# rca_studio_II_mutli_v5.net
KiCad netlist of a schematic drawn in EAGLE
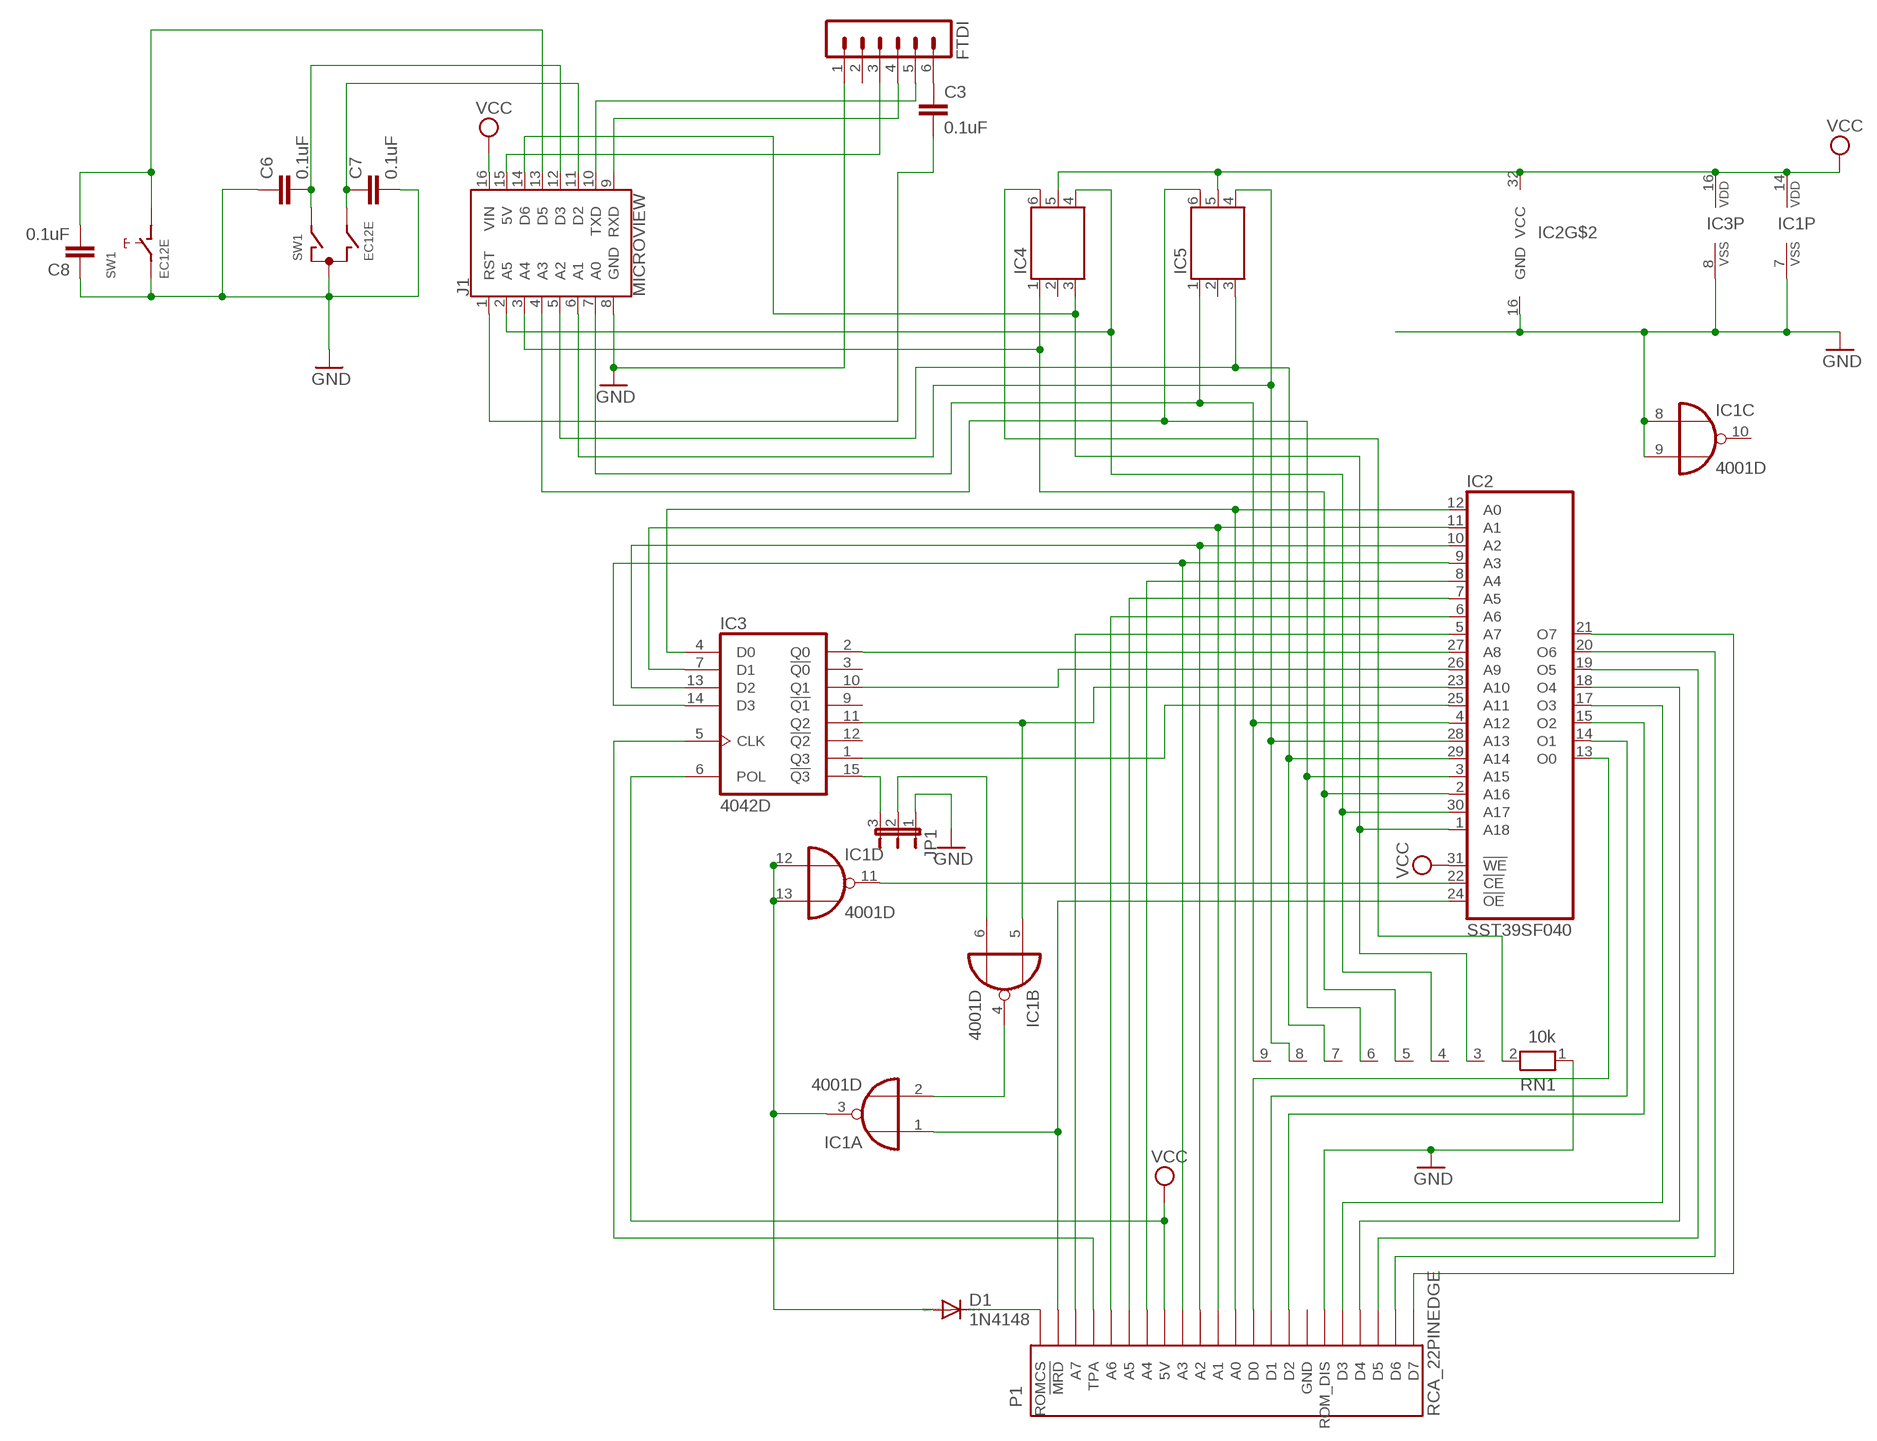
[diagram p0: schematic, sheet 1]

(export (version "E")
  (design (tool "Eeschema 10.0.6"))
  (components
    (comp (ref "C3")
      (value "0.1uF")
      (footprint "eagle-import:C0805")
      (libsource (lib "eagle-import") (part "C-EUC0805"))
    )
    (comp (ref "C6")
      (value "0.1uF")
      (footprint "eagle-import:C0805")
      (libsource (lib "eagle-import") (part "C-EUC0805"))
    )
    (comp (ref "C7")
      (value "0.1uF")
      (footprint "eagle-import:C0805")
      (libsource (lib "eagle-import") (part "C-EUC0805"))
    )
    (comp (ref "C8")
      (value "0.1uF")
      (footprint "eagle-import:C0805")
      (libsource (lib "eagle-import") (part "C-EUC0805"))
    )
    (comp (ref "D1")
      (value "1N4148")
      (footprint "eagle-import:DO35-7")
      (libsource (lib "eagle-import") (part "1N4148DO35-7"))
    )
    (comp (ref "FTDI")
      (value "MA06-1")
      (footprint "eagle-import:MA06-1")
      (libsource (lib "eagle-import") (part "MA06-1"))
    )
    (comp (ref "IC1")
      (value "4001D")
      (footprint "eagle-import:SO14")
      (libsource (lib "eagle-import") (part "4001D"))
    )
    (comp (ref "IC2")
      (value "SST39SF040")
      (footprint "eagle-import:S32")
      (libsource (lib "eagle-import") (part "SST39SF040"))
    )
    (comp (ref "IC3")
      (value "4042D")
      (footprint "eagle-import:SO16")
      (libsource (lib "eagle-import") (part "4042D"))
    )
    (comp (ref "IC4")
      (value "HEXENCODERHEXENCODER")
      (footprint "eagle-import:HEXENCODER")
      (libsource (lib "eagle-import") (part "HEXENCODERHEXENCODER"))
    )
    (comp (ref "IC5")
      (value "HEXENCODERHEXENCODER")
      (footprint "eagle-import:HEXENCODER")
      (libsource (lib "eagle-import") (part "HEXENCODERHEXENCODER"))
    )
    (comp (ref "J1")
      (value "MICROVIEW")
      (footprint "eagle-import:MV-DIP16-NODIMENSION")
      (libsource (lib "eagle-import") (part "MICROVIEW-16ND"))
    )
    (comp (ref "JP1")
      (value "JP2E")
      (footprint "eagle-import:JP2")
      (libsource (lib "eagle-import") (part "JP2E"))
    )
    (comp (ref "P1")
      (value "RCA_22PINEDGE")
      (footprint "eagle-import:RCA_22PINEDGE")
      (libsource (lib "eagle-import") (part "RCA_22PINEDGE"))
    )
    (comp (ref "RN1")
      (value "10k")
      (footprint "eagle-import:RN-9")
      (libsource (lib "eagle-import") (part "RN08"))
    )
    (comp (ref "SW1")
      (value "EC12E")
      (footprint "eagle-import:ALPS_EC12E_SW")
      (fields (field (name "MPN") "EC12E2424407"))
      (libsource (lib "eagle-import") (part "EC12E_SW"))
    )
  )
  (nets
    (net (code "1") (name "GND") (class "Default")
      (node (ref "C6") (pin "1") (pinfunction "1_1") (pintype "passive"))
      (node (ref "C7") (pin "2") (pinfunction "2_2") (pintype "passive"))
      (node (ref "C8") (pin "1") (pinfunction "1_1") (pintype "passive"))
      (node (ref "FTDI") (pin "1") (pinfunction "1_1") (pintype "passive"))
      (node (ref "IC1") (pin "7") (pinfunction "VSS_7") (pintype "power_in"))
      (node (ref "IC1") (pin "8") (pinfunction "I0_8") (pintype "input"))
      (node (ref "IC1") (pin "9") (pinfunction "I1_9") (pintype "input"))
      (node (ref "IC2") (pin "16") (pinfunction "GND_16") (pintype "power_in"))
      (node (ref "IC3") (pin "8") (pinfunction "VSS_8") (pintype "power_in"))
      (node (ref "J1") (pin "8") (pinfunction "GND_8") (pintype "power_in"))
      (node (ref "JP1") (pin "1") (pinfunction "1_1") (pintype "passive"))
      (node (ref "P1") (pin "6") (pinfunction "ROM_DIS_6") (pintype "passive"))
      (node (ref "RN1") (pin "1") (pinfunction "1_1") (pintype "passive"))
      (node (ref "SW1") (pin "C") (pinfunction "C_C") (pintype "passive"))
      (node (ref "SW1") (pin "E") (pinfunction "2_E") (pintype "passive"))
    )
    (net (code "2") (name "Net-(C3-Pad1)") (class "Default")
      (node (ref "C3") (pin "1") (pinfunction "1_1") (pintype "passive"))
      (node (ref "FTDI") (pin "6") (pinfunction "6_6") (pintype "passive"))
    )
    (net (code "3") (name "Net-(IC1A-I0)") (class "Default")
      (node (ref "IC1") (pin "1") (pinfunction "I0_1") (pintype "input"))
      (node (ref "IC2") (pin "24") (pinfunction "~{OE}_24") (pintype "input"))
      (node (ref "P1") (pin "21") (pinfunction "~{MRD}_21") (pintype "passive"))
    )
    (net (code "4") (name "Net-(IC1A-I1)") (class "Default")
      (node (ref "IC1") (pin "2") (pinfunction "I1_2") (pintype "input"))
      (node (ref "IC1") (pin "4") (pinfunction "O_4") (pintype "output"))
    )
    (net (code "5") (name "Net-(IC1A-O)") (class "Default")
      (node (ref "D1") (pin "A") (pinfunction "A_A") (pintype "passive"))
      (node (ref "IC1") (pin "12") (pinfunction "I0_12") (pintype "input"))
      (node (ref "IC1") (pin "13") (pinfunction "I1_13") (pintype "input"))
      (node (ref "IC1") (pin "3") (pinfunction "O_3") (pintype "output"))
    )
    (net (code "6") (name "Net-(IC1B-I0)") (class "Default")
      (node (ref "IC1") (pin "5") (pinfunction "I0_5") (pintype "input"))
      (node (ref "IC2") (pin "23") (pinfunction "A10_23") (pintype "input"))
      (node (ref "IC3") (pin "11") (pinfunction "Q2_11") (pintype "output"))
    )
    (net (code "7") (name "Net-(IC1B-I1)") (class "Default")
      (node (ref "IC1") (pin "6") (pinfunction "I1_6") (pintype "input"))
      (node (ref "JP1") (pin "2") (pinfunction "2_2") (pintype "passive"))
    )
    (net (code "8") (name "Net-(IC1D-O)") (class "Default")
      (node (ref "IC1") (pin "11") (pinfunction "O_11") (pintype "output"))
      (node (ref "IC2") (pin "22") (pinfunction "~{CE}_22") (pintype "input"))
    )
    (net (code "9") (name "Net-(IC2A-A0)") (class "Default")
      (node (ref "IC2") (pin "12") (pinfunction "A0_12") (pintype "input"))
      (node (ref "IC3") (pin "4") (pinfunction "D0_4") (pintype "input"))
      (node (ref "P1") (pin "11") (pinfunction "A0_11") (pintype "passive"))
    )
    (net (code "10") (name "Net-(IC2A-A1)") (class "Default")
      (node (ref "IC2") (pin "11") (pinfunction "A1_11") (pintype "input"))
      (node (ref "IC3") (pin "7") (pinfunction "D1_7") (pintype "input"))
      (node (ref "P1") (pin "12") (pinfunction "A1_12") (pintype "passive"))
    )
    (net (code "11") (name "Net-(IC2A-A2)") (class "Default")
      (node (ref "IC2") (pin "10") (pinfunction "A2_10") (pintype "input"))
      (node (ref "IC3") (pin "13") (pinfunction "D2_13") (pintype "input"))
      (node (ref "P1") (pin "13") (pinfunction "A2_13") (pintype "passive"))
    )
    (net (code "12") (name "Net-(IC2A-A3)") (class "Default")
      (node (ref "IC2") (pin "9") (pinfunction "A3_9") (pintype "input"))
      (node (ref "IC3") (pin "14") (pinfunction "D3_14") (pintype "input"))
      (node (ref "P1") (pin "14") (pinfunction "A3_14") (pintype "passive"))
    )
    (net (code "13") (name "Net-(IC2A-A4)") (class "Default")
      (node (ref "IC2") (pin "8") (pinfunction "A4_8") (pintype "input"))
      (node (ref "P1") (pin "16") (pinfunction "A4_16") (pintype "passive"))
    )
    (net (code "14") (name "Net-(IC2A-A5)") (class "Default")
      (node (ref "IC2") (pin "7") (pinfunction "A5_7") (pintype "input"))
      (node (ref "P1") (pin "17") (pinfunction "A5_17") (pintype "passive"))
    )
    (net (code "15") (name "Net-(IC2A-A6)") (class "Default")
      (node (ref "IC2") (pin "6") (pinfunction "A6_6") (pintype "input"))
      (node (ref "P1") (pin "18") (pinfunction "A6_18") (pintype "passive"))
    )
    (net (code "16") (name "Net-(IC2A-A7)") (class "Default")
      (node (ref "IC2") (pin "5") (pinfunction "A7_5") (pintype "input"))
      (node (ref "P1") (pin "20") (pinfunction "A7_20") (pintype "passive"))
    )
    (net (code "17") (name "Net-(IC2A-A8)") (class "Default")
      (node (ref "IC2") (pin "27") (pinfunction "A8_27") (pintype "input"))
      (node (ref "IC3") (pin "2") (pinfunction "Q0_2") (pintype "output"))
    )
    (net (code "18") (name "Net-(IC2A-A9)") (class "Default")
      (node (ref "IC2") (pin "26") (pinfunction "A9_26") (pintype "input"))
      (node (ref "IC3") (pin "10") (pinfunction "Q1_10") (pintype "output"))
    )
    (net (code "19") (name "Net-(IC2A-A11)") (class "Default")
      (node (ref "IC2") (pin "25") (pinfunction "A11_25") (pintype "input"))
      (node (ref "IC3") (pin "1") (pinfunction "Q3_1") (pintype "output"))
    )
    (net (code "20") (name "Net-(IC2A-A12)") (class "Default")
      (node (ref "IC2") (pin "4") (pinfunction "A12_4") (pintype "input"))
      (node (ref "IC5") (pin "1") (pinfunction "1_1") (pintype "passive"))
      (node (ref "J1") (pin "7") (pinfunction "A0_7") (pintype "output"))
      (node (ref "RN1") (pin "9") (pinfunction "9_9") (pintype "passive"))
    )
    (net (code "21") (name "Net-(IC2A-A13)") (class "Default")
      (node (ref "IC2") (pin "28") (pinfunction "A13_28") (pintype "input"))
      (node (ref "IC5") (pin "4") (pinfunction "2_4") (pintype "passive"))
      (node (ref "J1") (pin "6") (pinfunction "A1_6") (pintype "output"))
      (node (ref "RN1") (pin "8") (pinfunction "8_8") (pintype "passive"))
    )
    (net (code "22") (name "Net-(IC2A-A14)") (class "Default")
      (node (ref "IC2") (pin "29") (pinfunction "A14_29") (pintype "input"))
      (node (ref "IC5") (pin "3") (pinfunction "4_3") (pintype "passive"))
      (node (ref "J1") (pin "5") (pinfunction "A2_5") (pintype "output"))
      (node (ref "RN1") (pin "7") (pinfunction "7_7") (pintype "passive"))
    )
    (net (code "23") (name "Net-(IC2A-A15)") (class "Default")
      (node (ref "IC2") (pin "3") (pinfunction "A15_3") (pintype "input"))
      (node (ref "IC5") (pin "6") (pinfunction "8_6") (pintype "passive"))
      (node (ref "J1") (pin "4") (pinfunction "A3_4") (pintype "output"))
      (node (ref "RN1") (pin "6") (pinfunction "6_6") (pintype "passive"))
    )
    (net (code "24") (name "Net-(IC2A-A16)") (class "Default")
      (node (ref "IC2") (pin "2") (pinfunction "A16_2") (pintype "input"))
      (node (ref "IC4") (pin "1") (pinfunction "1_1") (pintype "passive"))
      (node (ref "J1") (pin "3") (pinfunction "A4_3") (pintype "output"))
      (node (ref "RN1") (pin "5") (pinfunction "5_5") (pintype "passive"))
    )
    (net (code "25") (name "Net-(IC2A-A17)") (class "Default")
      (node (ref "IC2") (pin "30") (pinfunction "A17_30") (pintype "input"))
      (node (ref "IC4") (pin "4") (pinfunction "2_4") (pintype "passive"))
      (node (ref "J1") (pin "2") (pinfunction "A5_2") (pintype "output"))
      (node (ref "RN1") (pin "4") (pinfunction "4_4") (pintype "passive"))
    )
    (net (code "26") (name "Net-(IC2A-A18)") (class "Default")
      (node (ref "IC2") (pin "1") (pinfunction "A18_1") (pintype "input"))
      (node (ref "IC4") (pin "3") (pinfunction "4_3") (pintype "passive"))
      (node (ref "J1") (pin "14") (pinfunction "D6_14") (pintype "output"))
      (node (ref "RN1") (pin "3") (pinfunction "3_3") (pintype "passive"))
    )
    (net (code "27") (name "Net-(IC2A-O0)") (class "Default")
      (node (ref "IC2") (pin "13") (pinfunction "O0_13") (pintype "tri_state"))
      (node (ref "P1") (pin "10") (pinfunction "D0_10") (pintype "passive"))
    )
    (net (code "28") (name "Net-(IC2A-O1)") (class "Default")
      (node (ref "IC2") (pin "14") (pinfunction "O1_14") (pintype "tri_state"))
      (node (ref "P1") (pin "9") (pinfunction "D1_9") (pintype "passive"))
    )
    (net (code "29") (name "Net-(IC2A-O2)") (class "Default")
      (node (ref "IC2") (pin "15") (pinfunction "O2_15") (pintype "tri_state"))
      (node (ref "P1") (pin "8") (pinfunction "D2_8") (pintype "passive"))
    )
    (net (code "30") (name "Net-(IC2A-O3)") (class "Default")
      (node (ref "IC2") (pin "17") (pinfunction "O3_17") (pintype "tri_state"))
      (node (ref "P1") (pin "5") (pinfunction "D3_5") (pintype "passive"))
    )
    (net (code "31") (name "Net-(IC2A-O4)") (class "Default")
      (node (ref "IC2") (pin "18") (pinfunction "O4_18") (pintype "tri_state"))
      (node (ref "P1") (pin "4") (pinfunction "D4_4") (pintype "passive"))
    )
    (net (code "32") (name "Net-(IC2A-O5)") (class "Default")
      (node (ref "IC2") (pin "19") (pinfunction "O5_19") (pintype "tri_state"))
      (node (ref "P1") (pin "3") (pinfunction "D5_3") (pintype "passive"))
    )
    (net (code "33") (name "Net-(IC2A-O6)") (class "Default")
      (node (ref "IC2") (pin "20") (pinfunction "O6_20") (pintype "tri_state"))
      (node (ref "P1") (pin "2") (pinfunction "D6_2") (pintype "passive"))
    )
    (net (code "34") (name "Net-(IC2A-O7)") (class "Default")
      (node (ref "IC2") (pin "21") (pinfunction "O7_21") (pintype "tri_state"))
      (node (ref "P1") (pin "1") (pinfunction "D7_1") (pintype "passive"))
    )
    (net (code "35") (name "Net-(IC3A-CLK)") (class "Default")
      (node (ref "IC3") (pin "5") (pinfunction "CLK_5") (pintype "input"))
      (node (ref "P1") (pin "19") (pinfunction "TPA_19") (pintype "passive"))
    )
    (net (code "36") (name "Net-(IC3A-~{Q3})") (class "Default")
      (node (ref "IC3") (pin "15") (pinfunction "~{Q3}_15") (pintype "output"))
      (node (ref "JP1") (pin "3") (pinfunction "3_3") (pintype "passive"))
    )
    (net (code "37") (name "Net-(IC4-8)") (class "Default")
      (node (ref "IC4") (pin "6") (pinfunction "8_6") (pintype "passive"))
      (node (ref "RN1") (pin "2") (pinfunction "2_2") (pintype "passive"))
    )
    (net (code "38") (name "Net-(J1-5V)") (class "Default")
      (node (ref "FTDI") (pin "3") (pinfunction "3_3") (pintype "passive"))
      (node (ref "J1") (pin "15") (pinfunction "5V_15") (pintype "output"))
    )
    (net (code "39") (name "Net-(J1-D2)") (class "Default")
      (node (ref "C7") (pin "1") (pinfunction "1_1") (pintype "passive"))
      (node (ref "J1") (pin "11") (pinfunction "D2_11") (pintype "output"))
      (node (ref "SW1") (pin "B") (pinfunction "B_B") (pintype "passive"))
    )
    (net (code "40") (name "Net-(J1-D3)") (class "Default")
      (node (ref "C6") (pin "2") (pinfunction "2_2") (pintype "passive"))
      (node (ref "J1") (pin "12") (pinfunction "D3_12") (pintype "output"))
      (node (ref "SW1") (pin "A") (pinfunction "A_A") (pintype "passive"))
    )
    (net (code "41") (name "Net-(J1-D5)") (class "Default")
      (node (ref "C8") (pin "2") (pinfunction "2_2") (pintype "passive"))
      (node (ref "J1") (pin "13") (pinfunction "D5_13") (pintype "output"))
      (node (ref "SW1") (pin "D") (pinfunction "1_D") (pintype "passive"))
    )
    (net (code "42") (name "Net-(J1-RST)") (class "Default")
      (node (ref "C3") (pin "2") (pinfunction "2_2") (pintype "passive"))
      (node (ref "J1") (pin "1") (pinfunction "RST_1") (pintype "output"))
    )
    (net (code "43") (name "Net-(J1-RXD)") (class "Default")
      (node (ref "FTDI") (pin "4") (pinfunction "4_4") (pintype "passive"))
      (node (ref "J1") (pin "9") (pinfunction "RXD_9") (pintype "output"))
    )
    (net (code "44") (name "Net-(J1-TXD)") (class "Default")
      (node (ref "FTDI") (pin "5") (pinfunction "5_5") (pintype "passive"))
      (node (ref "J1") (pin "10") (pinfunction "TXD_10") (pintype "output"))
    )
    (net (code "45") (name "Net-(P1-ROMCS)") (class "Default")
      (node (ref "D1") (pin "C") (pinfunction "C_C") (pintype "passive"))
      (node (ref "P1") (pin "22") (pinfunction "ROMCS_22") (pintype "passive"))
    )
    (net (code "46") (name "VCC") (class "Default")
      (node (ref "IC1") (pin "14") (pinfunction "VDD_14") (pintype "power_in"))
      (node (ref "IC2") (pin "31") (pinfunction "~{WE}_31") (pintype "input"))
      (node (ref "IC2") (pin "32") (pinfunction "VCC_32") (pintype "power_in"))
      (node (ref "IC3") (pin "16") (pinfunction "VDD_16") (pintype "power_in"))
      (node (ref "IC3") (pin "6") (pinfunction "POL_6") (pintype "input"))
      (node (ref "IC4") (pin "5") (pinfunction "C2_5") (pintype "passive"))
      (node (ref "IC5") (pin "5") (pinfunction "C2_5") (pintype "passive"))
      (node (ref "J1") (pin "16") (pinfunction "VIN_16") (pintype "passive"))
      (node (ref "P1") (pin "15") (pinfunction "5V_15") (pintype "passive"))
    )
    (net (code "47") (name "unconnected-(FTDI-Pad2)") (class "Default")
      (node (ref "FTDI") (pin "2") (pinfunction "2_2") (pintype "passive"))
    )
    (net (code "48") (name "unconnected-(IC1C-O-Pad10)") (class "Default")
      (node (ref "IC1") (pin "10") (pinfunction "O_10") (pintype "output"))
    )
    (net (code "49") (name "unconnected-(IC3A-~{Q0}-Pad3)") (class "Default")
      (node (ref "IC3") (pin "3") (pinfunction "~{Q0}_3") (pintype "output"))
    )
    (net (code "50") (name "unconnected-(IC3A-~{Q1}-Pad9)") (class "Default")
      (node (ref "IC3") (pin "9") (pinfunction "~{Q1}_9") (pintype "output"))
    )
    (net (code "51") (name "unconnected-(IC3A-~{Q2}-Pad12)") (class "Default")
      (node (ref "IC3") (pin "12") (pinfunction "~{Q2}_12") (pintype "output"))
    )
    (net (code "52") (name "unconnected-(IC4-C1-Pad2)") (class "Default")
      (node (ref "IC4") (pin "2") (pinfunction "C1_2") (pintype "passive"))
    )
    (net (code "53") (name "unconnected-(IC5-C1-Pad2)") (class "Default")
      (node (ref "IC5") (pin "2") (pinfunction "C1_2") (pintype "passive"))
    )
    (net (code "54") (name "unconnected-(P1-GND-Pad7)") (class "Default")
      (node (ref "P1") (pin "7") (pinfunction "GND_7") (pintype "passive"))
    )
  )
)
